# OpAmp-breakout-ABC.net
KiCad netlist of a schematic drawn in EAGLE
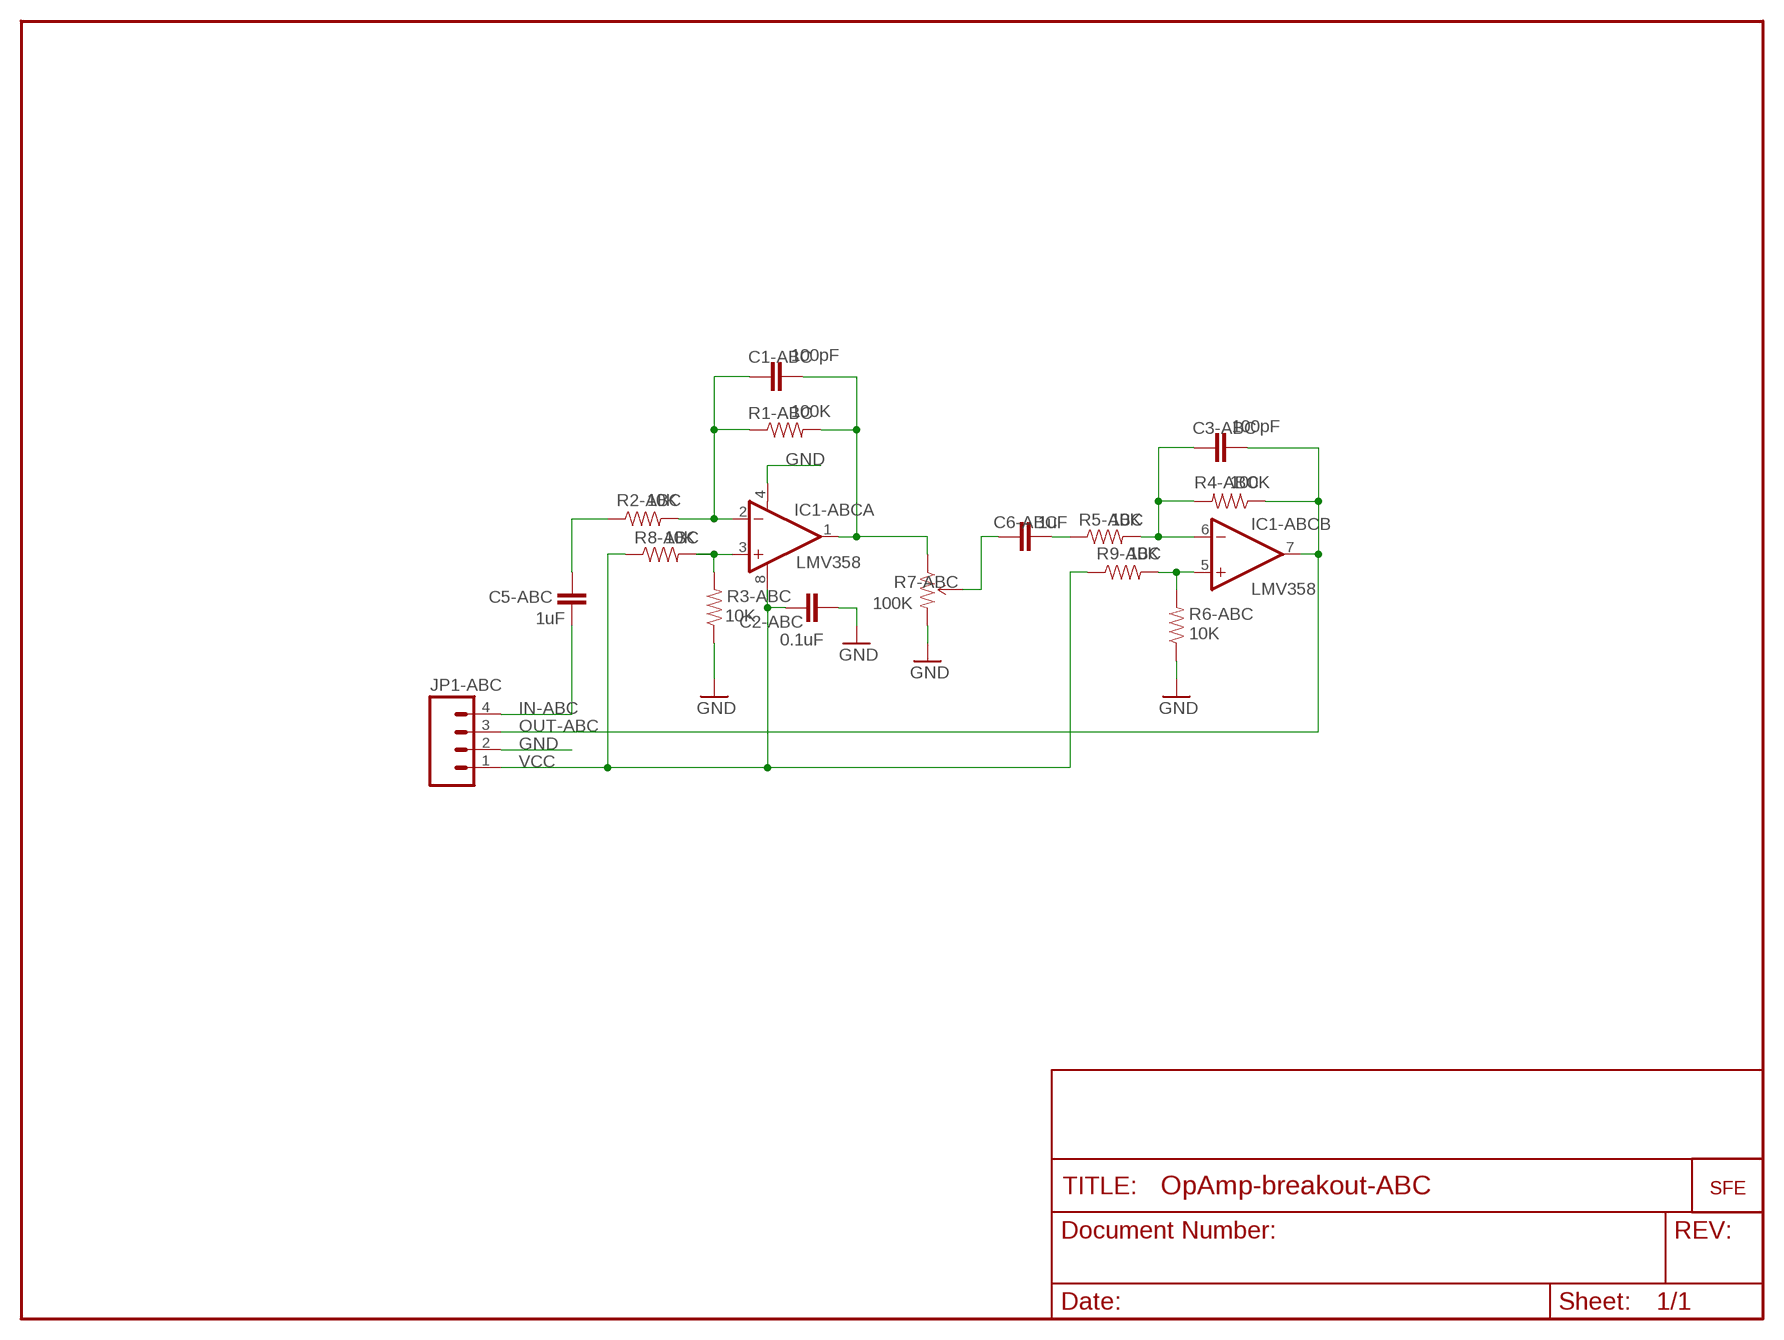
[diagram p0: schematic, sheet 1]

(export (version "E")
  (design (tool "Eeschema 10.0.6"))
  (components
    (comp (ref "C1-ABC")
      (value "100pF")
      (footprint "eagle-import:C0402")
      (libsource (lib "eagle-import") (part "CAP0402"))
    )
    (comp (ref "C2-ABC")
      (value "0.1uF")
      (footprint "eagle-import:C0402")
      (libsource (lib "eagle-import") (part "CAP0402"))
    )
    (comp (ref "C3-ABC")
      (value "100pF")
      (footprint "eagle-import:C0402")
      (libsource (lib "eagle-import") (part "CAP0402"))
    )
    (comp (ref "C5-ABC")
      (value "1uF")
      (footprint "eagle-import:C0402")
      (libsource (lib "eagle-import") (part "CAP0402"))
    )
    (comp (ref "C6-ABC")
      (value "1uF")
      (footprint "eagle-import:C0402")
      (libsource (lib "eagle-import") (part "CAP0402"))
    )
    (comp (ref "IC1-ABC")
      (value "LMV358")
      (footprint "eagle-import:SO08")
      (libsource (lib "eagle-import") (part "OPAMP-DUALU"))
    )
    (comp (ref "JP1-ABC")
      (value "M04PTH")
      (footprint "eagle-import:1X04")
      (libsource (lib "eagle-import") (part "M04PTH"))
    )
    (comp (ref "R1-ABC")
      (value "100K")
      (footprint "eagle-import:C0402")
      (libsource (lib "eagle-import") (part "RESISTOR0402"))
    )
    (comp (ref "R2-ABC")
      (value "10K")
      (footprint "eagle-import:C0402")
      (libsource (lib "eagle-import") (part "RESISTOR0402"))
    )
    (comp (ref "R3-ABC")
      (value "10K")
      (footprint "eagle-import:C0402")
      (libsource (lib "eagle-import") (part "RESISTOR0402"))
    )
    (comp (ref "R4-ABC")
      (value "100K")
      (footprint "eagle-import:C0402")
      (libsource (lib "eagle-import") (part "RESISTOR0402"))
    )
    (comp (ref "R5-ABC")
      (value "10K")
      (footprint "eagle-import:C0402")
      (libsource (lib "eagle-import") (part "RESISTOR0402"))
    )
    (comp (ref "R6-ABC")
      (value "10K")
      (footprint "eagle-import:C0402")
      (libsource (lib "eagle-import") (part "RESISTOR0402"))
    )
    (comp (ref "R7-ABC")
      (value "100K")
      (footprint "eagle-import:TRIMPOT-3MM")
      (libsource (lib "eagle-import") (part "TRIMPOTSMD"))
    )
    (comp (ref "R8-ABC")
      (value "10K")
      (footprint "eagle-import:C0402")
      (libsource (lib "eagle-import") (part "SparkFun-DC_RESISTOR0402"))
    )
    (comp (ref "R9-ABC")
      (value "10K")
      (footprint "eagle-import:C0402")
      (libsource (lib "eagle-import") (part "SparkFun-DC_RESISTOR0402"))
    )
    (comp (ref "U$3-ABC")
      (value "LOGO-SFENEW")
      (footprint "eagle-import:SFE-NEW-WEBLOGO")
      (libsource (lib "eagle-import") (part "LOGO-SFENEW"))
    )
  )
  (nets
    (net (code "1") (name "/IN-ABC") (class "Default")
      (node (ref "C5-ABC") (pin "1") (pinfunction "1_1") (pintype "passive"))
      (node (ref "JP1-ABC") (pin "4") (pinfunction "4_4") (pintype "passive"))
    )
    (net (code "2") (name "/OUT-ABC") (class "Default")
      (node (ref "C3-ABC") (pin "2") (pinfunction "2_2") (pintype "passive"))
      (node (ref "IC1-ABC") (pin "7") (pinfunction "OUT_7") (pintype "output"))
      (node (ref "JP1-ABC") (pin "3") (pinfunction "3_3") (pintype "passive"))
      (node (ref "R4-ABC") (pin "1") (pinfunction "1_1") (pintype "passive"))
    )
    (net (code "3") (name "/VCC") (class "Default")
      (node (ref "C2-ABC") (pin "1") (pinfunction "1_1") (pintype "passive"))
      (node (ref "IC1-ABC") (pin "8") (pinfunction "V+_8") (pintype "power_in"))
      (node (ref "JP1-ABC") (pin "1") (pinfunction "1_1") (pintype "passive"))
      (node (ref "R8-ABC") (pin "1") (pinfunction "1_1") (pintype "passive"))
      (node (ref "R9-ABC") (pin "1") (pinfunction "1_1") (pintype "passive"))
    )
    (net (code "4") (name "GND") (class "Default")
      (node (ref "C2-ABC") (pin "2") (pinfunction "2_2") (pintype "passive"))
      (node (ref "IC1-ABC") (pin "4") (pinfunction "V-_4") (pintype "power_in"))
      (node (ref "JP1-ABC") (pin "2") (pinfunction "2_2") (pintype "passive"))
      (node (ref "R3-ABC") (pin "1") (pinfunction "1_1") (pintype "passive"))
      (node (ref "R6-ABC") (pin "1") (pinfunction "1_1") (pintype "passive"))
      (node (ref "R7-ABC") (pin "3") (pinfunction "CW_3") (pintype "passive"))
    )
    (net (code "5") (name "Net-(C5-ABC-Pad2)") (class "Default")
      (node (ref "C5-ABC") (pin "2") (pinfunction "2_2") (pintype "passive"))
      (node (ref "R2-ABC") (pin "1") (pinfunction "1_1") (pintype "passive"))
    )
    (net (code "6") (name "Net-(C6-ABC-Pad1)") (class "Default")
      (node (ref "C6-ABC") (pin "1") (pinfunction "1_1") (pintype "passive"))
      (node (ref "R5-ABC") (pin "1") (pinfunction "1_1") (pintype "passive"))
    )
    (net (code "7") (name "Net-(IC1-ABCA-+IN)") (class "Default")
      (node (ref "IC1-ABC") (pin "3") (pinfunction "+IN_3") (pintype "input"))
      (node (ref "R3-ABC") (pin "2") (pinfunction "2_2") (pintype "passive"))
      (node (ref "R8-ABC") (pin "2") (pinfunction "2_2") (pintype "passive"))
    )
    (net (code "8") (name "Net-(IC1-ABCA--IN)") (class "Default")
      (node (ref "C1-ABC") (pin "1") (pinfunction "1_1") (pintype "passive"))
      (node (ref "IC1-ABC") (pin "2") (pinfunction "-IN_2") (pintype "input"))
      (node (ref "R1-ABC") (pin "1") (pinfunction "1_1") (pintype "passive"))
      (node (ref "R2-ABC") (pin "2") (pinfunction "2_2") (pintype "passive"))
    )
    (net (code "9") (name "Net-(IC1-ABCA-OUT)") (class "Default")
      (node (ref "C1-ABC") (pin "2") (pinfunction "2_2") (pintype "passive"))
      (node (ref "IC1-ABC") (pin "1") (pinfunction "OUT_1") (pintype "output"))
      (node (ref "R1-ABC") (pin "2") (pinfunction "2_2") (pintype "passive"))
      (node (ref "R7-ABC") (pin "1") (pinfunction "CCW_1") (pintype "passive"))
    )
    (net (code "10") (name "Net-(IC1-ABCB-+IN)") (class "Default")
      (node (ref "IC1-ABC") (pin "5") (pinfunction "+IN_5") (pintype "input"))
      (node (ref "R6-ABC") (pin "2") (pinfunction "2_2") (pintype "passive"))
      (node (ref "R9-ABC") (pin "2") (pinfunction "2_2") (pintype "passive"))
    )
    (net (code "11") (name "Net-(IC1-ABCB--IN)") (class "Default")
      (node (ref "C3-ABC") (pin "1") (pinfunction "1_1") (pintype "passive"))
      (node (ref "IC1-ABC") (pin "6") (pinfunction "-IN_6") (pintype "input"))
      (node (ref "R4-ABC") (pin "2") (pinfunction "2_2") (pintype "passive"))
      (node (ref "R5-ABC") (pin "2") (pinfunction "2_2") (pintype "passive"))
    )
    (net (code "12") (name "Net-(R7-ABC-WIPER)") (class "Default")
      (node (ref "C6-ABC") (pin "2") (pinfunction "2_2") (pintype "passive"))
      (node (ref "R7-ABC") (pin "2") (pinfunction "WIPER_2") (pintype "passive"))
    )
  )
)
